# i2c-ir.net
KiCad netlist of a schematic drawn in EAGLE
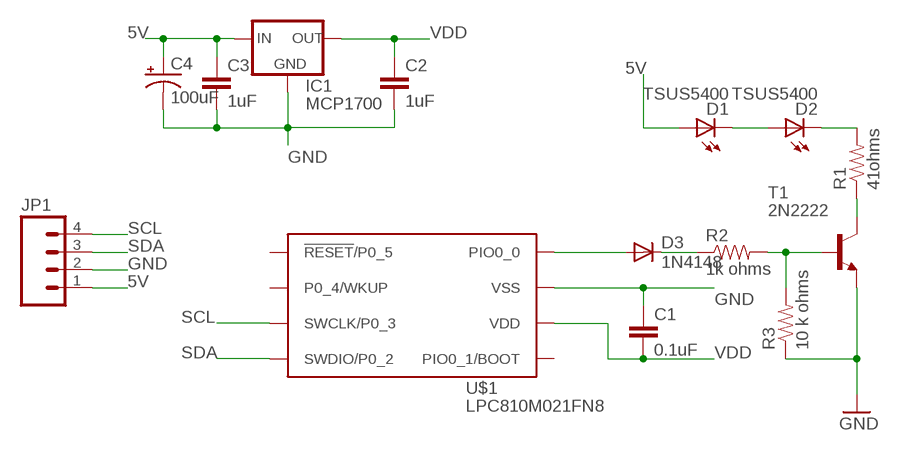
[diagram p0: schematic, sheet 1]

(export (version "E")
  (design (tool "Eeschema 10.0.6"))
  (components
    (comp (ref "C1")
      (value "0.1uF")
      (footprint "eagle-import:CAP-PTH-SMALL")
      (libsource (lib "eagle-import") (part "CAPPTH"))
    )
    (comp (ref "C2")
      (value "1uF")
      (footprint "eagle-import:CAP-PTH-SMALL")
      (libsource (lib "eagle-import") (part "SparkFun-Passives_CAPPTH"))
    )
    (comp (ref "C3")
      (value "1uF")
      (footprint "eagle-import:CAP-PTH-SMALL")
      (libsource (lib "eagle-import") (part "SparkFun-Passives_CAPPTH"))
    )
    (comp (ref "C4")
      (value "100uF")
      (footprint "eagle-import:CPOL-RADIAL-100UF-25V")
      (libsource (lib "eagle-import") (part "CAP_POLPTH1"))
    )
    (comp (ref "D1")
      (value "TSUS5400")
      (footprint "eagle-import:SFH482")
      (libsource (lib "eagle-import") (part "SFH482"))
    )
    (comp (ref "D2")
      (value "TSUS5400")
      (footprint "eagle-import:SFH482")
      (libsource (lib "eagle-import") (part "SFH482"))
    )
    (comp (ref "D3")
      (value "1N4148")
      (footprint "eagle-import:DO35-7")
      (libsource (lib "eagle-import") (part "1N4148DO35-7"))
    )
    (comp (ref "IC1")
      (value "MCP1700")
      (footprint "eagle-import:TO92-INLINE")
      (libsource (lib "eagle-import") (part "MCP1700INLINE"))
    )
    (comp (ref "JP1")
      (value "M04PTH")
      (footprint "eagle-import:1X04")
      (libsource (lib "eagle-import") (part "M04PTH"))
    )
    (comp (ref "R1")
      (value "41ohms")
      (footprint "eagle-import:AXIAL-0.3")
      (libsource (lib "eagle-import") (part "RESISTORAXIAL-0.3"))
    )
    (comp (ref "R2")
      (value "1k ohms")
      (footprint "eagle-import:AXIAL-0.3")
      (libsource (lib "eagle-import") (part "RESISTORAXIAL-0.3"))
    )
    (comp (ref "R3")
      (value "10 k ohms")
      (footprint "eagle-import:AXIAL-0.3")
      (libsource (lib "eagle-import") (part "RESISTORAXIAL-0.3"))
    )
    (comp (ref "T1")
      (value "2N2222")
      (footprint "eagle-import:TO92-EBC-OVAL")
      (libsource (lib "eagle-import") (part "2N2222"))
    )
    (comp (ref "U$1")
      (value "LPC810M021FN8")
      (footprint "eagle-import:DIP8")
      (libsource (lib "eagle-import") (part "LPC810M021FN8"))
    )
  )
  (nets
    (net (code "1") (name "/5V") (class "Default")
      (node (ref "C3") (pin "1") (pinfunction "1_1") (pintype "passive"))
      (node (ref "C4") (pin "1") (pinfunction "+_1") (pintype "passive"))
      (node (ref "D1") (pin "A") (pinfunction "A_A") (pintype "passive"))
      (node (ref "IC1") (pin "2") (pinfunction "IN_2") (pintype "input"))
      (node (ref "JP1") (pin "1") (pinfunction "1_1") (pintype "passive"))
    )
    (net (code "2") (name "/SCL") (class "Default")
      (node (ref "JP1") (pin "4") (pinfunction "4_4") (pintype "passive"))
      (node (ref "U$1") (pin "P$3") (pinfunction "SWCLK/P0_3_P$3") (pintype "bidirectional"))
    )
    (net (code "3") (name "/SDA") (class "Default")
      (node (ref "JP1") (pin "3") (pinfunction "3_3") (pintype "passive"))
      (node (ref "U$1") (pin "P$4") (pinfunction "SWDIO/P0_2_P$4") (pintype "bidirectional"))
    )
    (net (code "4") (name "/VDD") (class "Default")
      (node (ref "C1") (pin "2") (pinfunction "2_2") (pintype "passive"))
      (node (ref "C2") (pin "1") (pinfunction "1_1") (pintype "passive"))
      (node (ref "IC1") (pin "3") (pinfunction "OUT_3") (pintype "passive"))
      (node (ref "U$1") (pin "P$6") (pinfunction "VDD_P$6") (pintype "bidirectional"))
    )
    (net (code "5") (name "GND") (class "Default")
      (node (ref "C1") (pin "1") (pinfunction "1_1") (pintype "passive"))
      (node (ref "C2") (pin "2") (pinfunction "2_2") (pintype "passive"))
      (node (ref "C3") (pin "2") (pinfunction "2_2") (pintype "passive"))
      (node (ref "C4") (pin "2") (pinfunction "-_2") (pintype "passive"))
      (node (ref "IC1") (pin "1") (pinfunction "GND_1") (pintype "input"))
      (node (ref "JP1") (pin "2") (pinfunction "2_2") (pintype "passive"))
      (node (ref "R3") (pin "P$1") (pinfunction "1_P$1") (pintype "passive"))
      (node (ref "T1") (pin "E") (pinfunction "E_E") (pintype "passive"))
      (node (ref "U$1") (pin "P$7") (pinfunction "VSS_P$7") (pintype "bidirectional"))
    )
    (net (code "6") (name "Net-(D1-C)") (class "Default")
      (node (ref "D1") (pin "K") (pinfunction "C_K") (pintype "passive"))
      (node (ref "D2") (pin "A") (pinfunction "A_A") (pintype "passive"))
    )
    (net (code "7") (name "Net-(D2-C)") (class "Default")
      (node (ref "D2") (pin "K") (pinfunction "C_K") (pintype "passive"))
      (node (ref "R1") (pin "P$2") (pinfunction "2_P$2") (pintype "passive"))
    )
    (net (code "8") (name "Net-(R1-1)") (class "Default")
      (node (ref "R1") (pin "P$1") (pinfunction "1_P$1") (pintype "passive"))
      (node (ref "T1") (pin "C") (pinfunction "C_C") (pintype "passive"))
    )
    (net (code "9") (name "Net-(R2-1)") (class "Default")
      (node (ref "D3") (pin "C") (pinfunction "C_C") (pintype "passive"))
      (node (ref "R2") (pin "P$1") (pinfunction "1_P$1") (pintype "passive"))
    )
    (net (code "10") (name "Net-(R2-2)") (class "Default")
      (node (ref "R2") (pin "P$2") (pinfunction "2_P$2") (pintype "passive"))
      (node (ref "R3") (pin "P$2") (pinfunction "2_P$2") (pintype "passive"))
      (node (ref "T1") (pin "B") (pinfunction "B_B") (pintype "passive"))
    )
    (net (code "11") (name "Net-(U$1-PIO0_0)") (class "Default")
      (node (ref "D3") (pin "A") (pinfunction "A_A") (pintype "passive"))
      (node (ref "U$1") (pin "P$8") (pinfunction "PIO0_0_P$8") (pintype "bidirectional"))
    )
    (net (code "12") (name "unconnected-(U$1-P0_4{slash}WKUP-PadP$2)") (class "Default")
      (node (ref "U$1") (pin "P$2") (pinfunction "P0_4/WKUP_P$2") (pintype "bidirectional"))
    )
    (net (code "13") (name "unconnected-(U$1-PIO0_1{slash}BOOT-PadP$5)") (class "Default")
      (node (ref "U$1") (pin "P$5") (pinfunction "PIO0_1/BOOT_P$5") (pintype "bidirectional"))
    )
    (net (code "14") (name "unconnected-(U$1-~{RESET}{slash}P0_5-PadP$1)") (class "Default")
      (node (ref "U$1") (pin "P$1") (pinfunction "~{RESET}/P0_5_P$1") (pintype "bidirectional"))
    )
  )
)
